# picstick_uart_rpi4.net
KiCad netlist of a schematic drawn in EAGLE
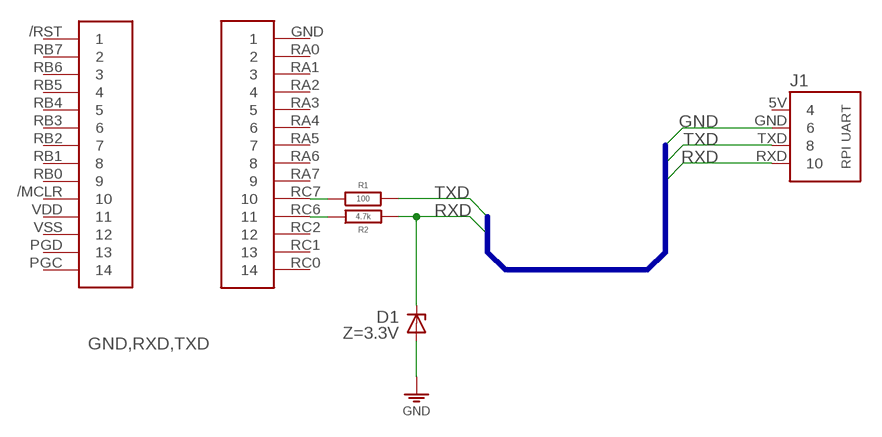
[diagram p0: schematic, sheet 1]

(export (version "E")
  (design (tool "Eeschema 10.0.6"))
  (components
    (comp (ref "D1")
      (value "Z=3.3V")
      (footprint "eagle-import:DO34Z10")
      (libsource (lib "eagle-import") (part "Z-DIODE34Z10"))
    )
    (comp (ref "J1")
      (value "RPI-UART-RPI4")
      (footprint "eagle-import:RPI-UART")
      (libsource (lib "eagle-import") (part "RPI-UART-RPI4"))
    )
    (comp (ref "J2")
      (value "PICSTICK")
      (footprint "eagle-import:PICSTICK_ALT")
      (libsource (lib "eagle-import") (part "PICSTICK"))
    )
    (comp (ref "R1")
      (value "100")
      (footprint "eagle-import:0204_12")
      (libsource (lib "eagle-import") (part "R-H0204/12"))
    )
    (comp (ref "R2")
      (value "4.7k")
      (footprint "eagle-import:0204_12")
      (libsource (lib "eagle-import") (part "R-H0204/12"))
    )
  )
  (nets
    (net (code "1") (name "/RXD") (class "Default")
      (node (ref "D1") (pin "C") (pinfunction "C_C") (pintype "passive"))
      (node (ref "J1") (pin "RXD") (pinfunction "10_RXD") (pintype "passive"))
      (node (ref "R2") (pin "2") (pinfunction "2_2") (pintype "passive"))
    )
    (net (code "2") (name "/TXD") (class "Default")
      (node (ref "J1") (pin "TXD") (pinfunction "8_TXD") (pintype "passive"))
      (node (ref "R1") (pin "2") (pinfunction "2_2") (pintype "passive"))
    )
    (net (code "4") (name "GND") (class "Default")
      (node (ref "D1") (pin "A") (pinfunction "A_A") (pintype "passive"))
      (node (ref "J1") (pin "GND") (pinfunction "6_GND") (pintype "passive"))
    )
    (net (code "5") (name "Net-(J2B-10)") (class "Default")
      (node (ref "J2") (pin "RC7") (pinfunction "10_RC7") (pintype "bidirectional"))
      (node (ref "R1") (pin "1") (pinfunction "1_1") (pintype "passive"))
    )
    (net (code "6") (name "Net-(J2B-11)") (class "Default")
      (node (ref "J2") (pin "RC6") (pinfunction "11_RC6") (pintype "bidirectional"))
      (node (ref "R2") (pin "1") (pinfunction "1_1") (pintype "passive"))
    )
    (net (code "7") (name "unconnected-(J1-4-Pad5V)") (class "Default")
      (node (ref "J1") (pin "5V") (pinfunction "4_5V") (pintype "passive"))
    )
    (net (code "8") (name "unconnected-(J2A-1-Pad{slash}RST)") (class "Default")
      (node (ref "J2") (pin "/RST") (pinfunction "1_/RST") (pintype "bidirectional"))
    )
    (net (code "9") (name "unconnected-(J2A-2-PadRB7)") (class "Default")
      (node (ref "J2") (pin "RB7") (pinfunction "2_RB7") (pintype "bidirectional"))
    )
    (net (code "10") (name "unconnected-(J2A-3-PadRB6)") (class "Default")
      (node (ref "J2") (pin "RB6") (pinfunction "3_RB6") (pintype "bidirectional"))
    )
    (net (code "11") (name "unconnected-(J2A-4-PadRB5)") (class "Default")
      (node (ref "J2") (pin "RB5") (pinfunction "4_RB5") (pintype "bidirectional"))
    )
    (net (code "12") (name "unconnected-(J2A-5-PadRB4)") (class "Default")
      (node (ref "J2") (pin "RB4") (pinfunction "5_RB4") (pintype "bidirectional"))
    )
    (net (code "13") (name "unconnected-(J2A-6-PadRB3)") (class "Default")
      (node (ref "J2") (pin "RB3") (pinfunction "6_RB3") (pintype "bidirectional"))
    )
    (net (code "14") (name "unconnected-(J2A-7-PadRB2)") (class "Default")
      (node (ref "J2") (pin "RB2") (pinfunction "7_RB2") (pintype "bidirectional"))
    )
    (net (code "15") (name "unconnected-(J2A-8-PadRB1)") (class "Default")
      (node (ref "J2") (pin "RB1") (pinfunction "8_RB1") (pintype "bidirectional"))
    )
    (net (code "16") (name "unconnected-(J2A-9-PadRB0)") (class "Default")
      (node (ref "J2") (pin "RB0") (pinfunction "9_RB0") (pintype "bidirectional"))
    )
    (net (code "17") (name "unconnected-(J2A-10-Pad{slash}MCLR)") (class "Default")
      (node (ref "J2") (pin "/MCLR") (pinfunction "10_/MCLR") (pintype "bidirectional"))
    )
    (net (code "18") (name "unconnected-(J2A-11-PadVDD)") (class "Default")
      (node (ref "J2") (pin "VDD") (pinfunction "11_VDD") (pintype "bidirectional"))
    )
    (net (code "19") (name "unconnected-(J2A-12-PadVSS)") (class "Default")
      (node (ref "J2") (pin "VSS") (pinfunction "12_VSS") (pintype "bidirectional"))
    )
    (net (code "20") (name "unconnected-(J2A-13-PadPGD)") (class "Default")
      (node (ref "J2") (pin "PGD") (pinfunction "13_PGD") (pintype "bidirectional"))
    )
    (net (code "21") (name "unconnected-(J2A-14-PadPGC)") (class "Default")
      (node (ref "J2") (pin "PGC") (pinfunction "14_PGC") (pintype "bidirectional"))
    )
    (net (code "22") (name "unconnected-(J2B-1-PadGND)") (class "Default")
      (node (ref "J2") (pin "GND") (pinfunction "1_GND") (pintype "bidirectional"))
    )
    (net (code "23") (name "unconnected-(J2B-2-PadRA0)") (class "Default")
      (node (ref "J2") (pin "RA0") (pinfunction "2_RA0") (pintype "bidirectional"))
    )
    (net (code "24") (name "unconnected-(J2B-3-PadRA1)") (class "Default")
      (node (ref "J2") (pin "RA1") (pinfunction "3_RA1") (pintype "bidirectional"))
    )
    (net (code "25") (name "unconnected-(J2B-4-PadRA2)") (class "Default")
      (node (ref "J2") (pin "RA2") (pinfunction "4_RA2") (pintype "bidirectional"))
    )
    (net (code "26") (name "unconnected-(J2B-5-PadRA3)") (class "Default")
      (node (ref "J2") (pin "RA3") (pinfunction "5_RA3") (pintype "bidirectional"))
    )
    (net (code "27") (name "unconnected-(J2B-6-PadRA4)") (class "Default")
      (node (ref "J2") (pin "RA4") (pinfunction "6_RA4") (pintype "bidirectional"))
    )
    (net (code "28") (name "unconnected-(J2B-7-PadRA5)") (class "Default")
      (node (ref "J2") (pin "RA5") (pinfunction "7_RA5") (pintype "bidirectional"))
    )
    (net (code "29") (name "unconnected-(J2B-8-PadRA6)") (class "Default")
      (node (ref "J2") (pin "RA6") (pinfunction "8_RA6") (pintype "bidirectional"))
    )
    (net (code "30") (name "unconnected-(J2B-9-PadRA7)") (class "Default")
      (node (ref "J2") (pin "RA7") (pinfunction "9_RA7") (pintype "bidirectional"))
    )
    (net (code "31") (name "unconnected-(J2B-12-PadRC2)") (class "Default")
      (node (ref "J2") (pin "RC2") (pinfunction "12_RC2") (pintype "bidirectional"))
    )
    (net (code "32") (name "unconnected-(J2B-13-PadRC1)") (class "Default")
      (node (ref "J2") (pin "RC1") (pinfunction "13_RC1") (pintype "bidirectional"))
    )
    (net (code "33") (name "unconnected-(J2B-14-PadRC0)") (class "Default")
      (node (ref "J2") (pin "RC0") (pinfunction "14_RC0") (pintype "bidirectional"))
    )
  )
)
